# ballanced_detector.net
KiCad netlist of a schematic drawn in EAGLE
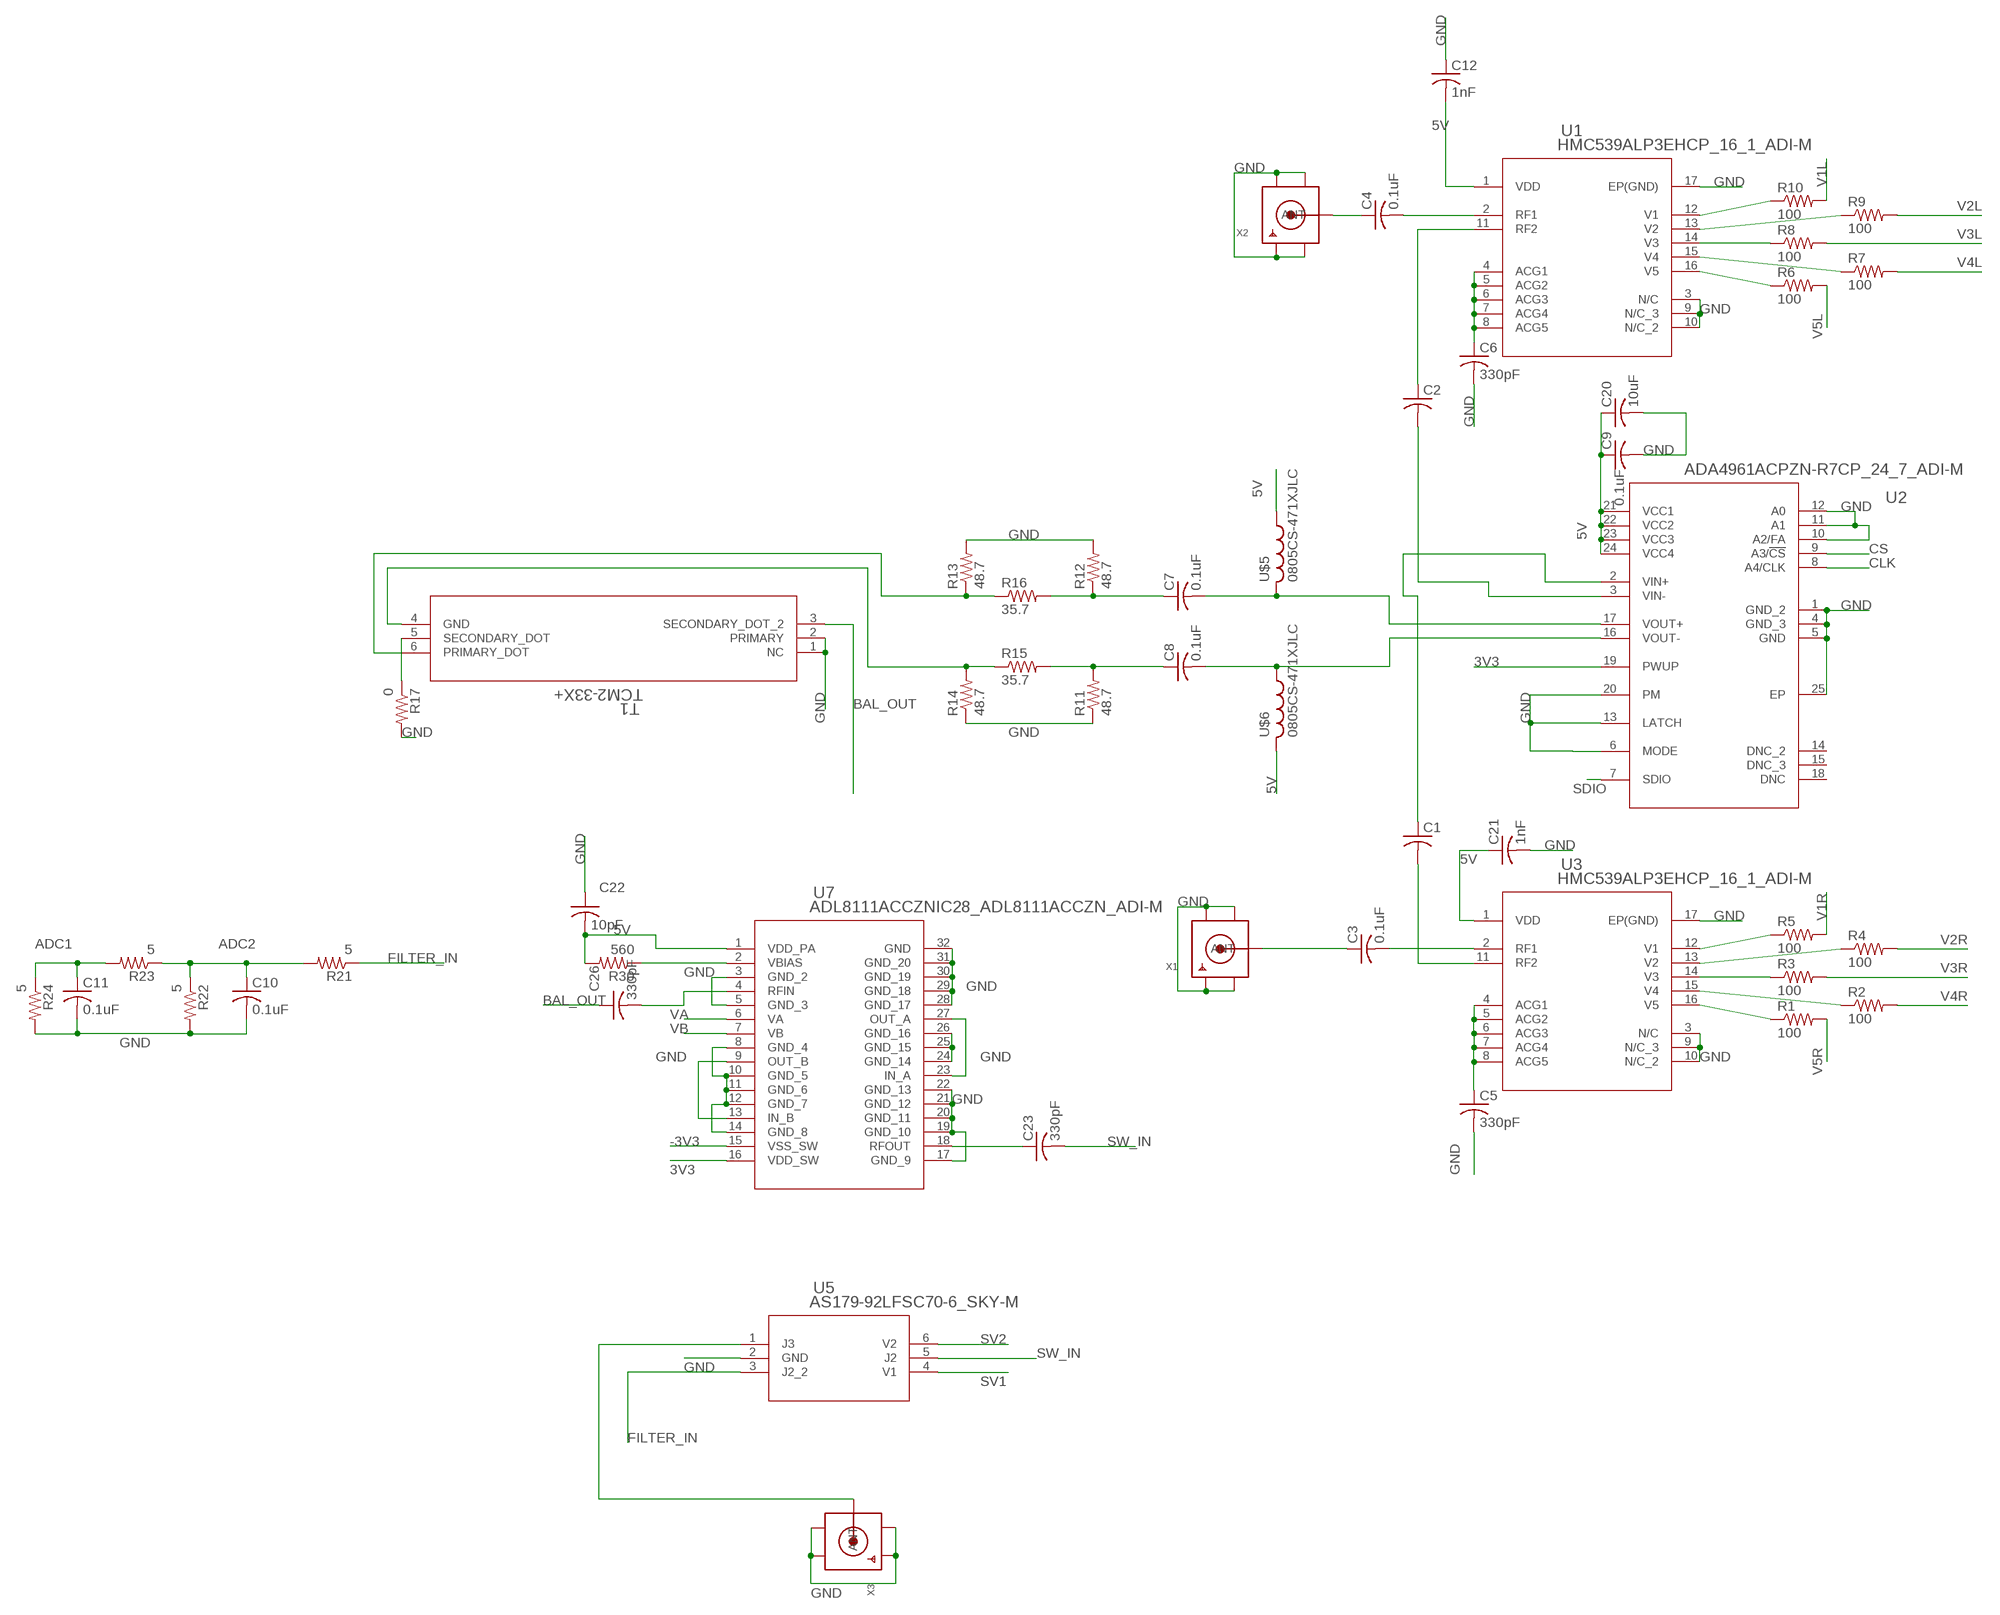
[diagram p0: schematic, sheet 1, part 1 of 2]
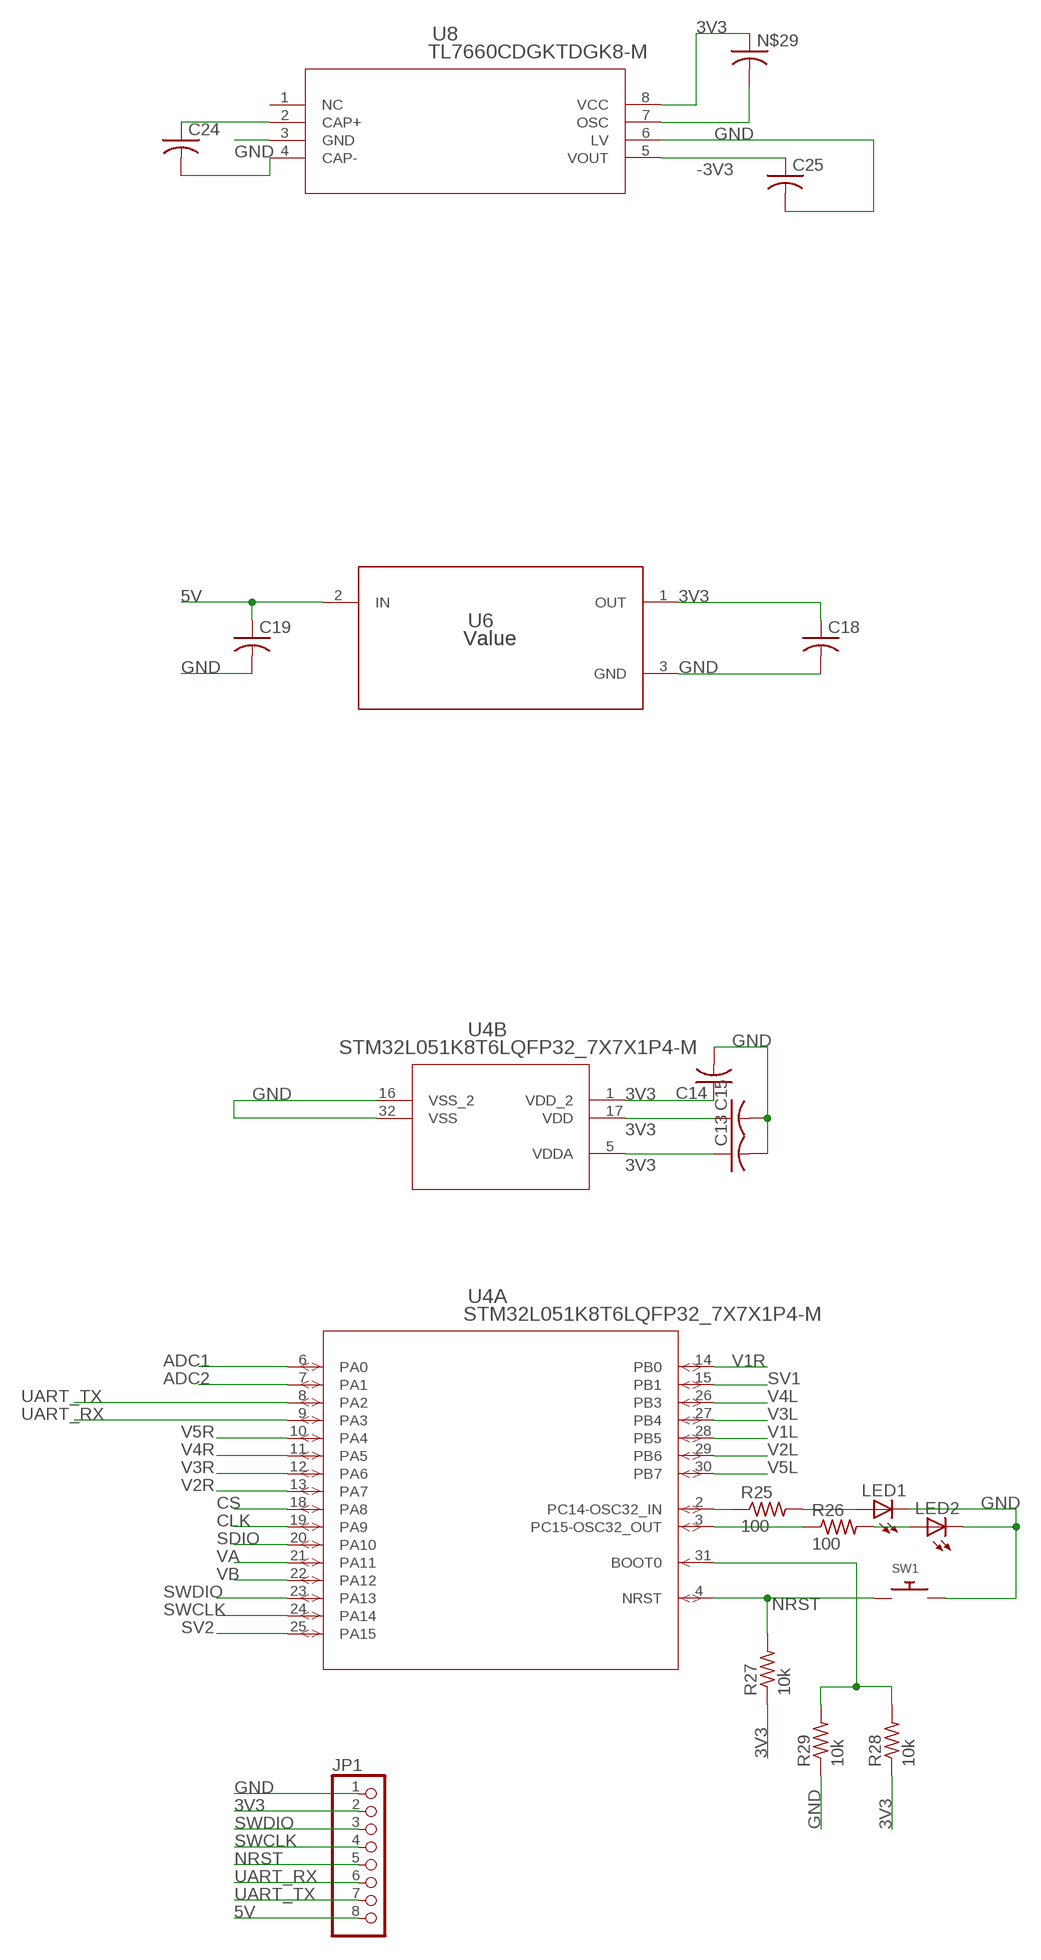
[diagram p1: schematic, sheet 1, part 2 of 2]

(export (version "E")
  (design (tool "Eeschema 10.0.6"))
  (components
    (comp (ref "C1")
      (value "C-USC0402")
      (footprint "eagle-import:C0402")
      (libsource (lib "eagle-import") (part "C-USC0402"))
    )
    (comp (ref "C2")
      (value "C-USC0402")
      (footprint "eagle-import:C0402")
      (libsource (lib "eagle-import") (part "C-USC0402"))
    )
    (comp (ref "C3")
      (value "0.1uF")
      (footprint "eagle-import:C0402")
      (libsource (lib "eagle-import") (part "C-USC0402"))
    )
    (comp (ref "C4")
      (value "0.1uF")
      (footprint "eagle-import:C0402")
      (libsource (lib "eagle-import") (part "C-USC0402"))
    )
    (comp (ref "C5")
      (value "330pF")
      (footprint "eagle-import:C0402")
      (libsource (lib "eagle-import") (part "C-USC0402"))
    )
    (comp (ref "C6")
      (value "330pF")
      (footprint "eagle-import:C0402")
      (libsource (lib "eagle-import") (part "C-USC0402"))
    )
    (comp (ref "C7")
      (value "0.1uF")
      (footprint "eagle-import:C0402")
      (libsource (lib "eagle-import") (part "C-USC0402"))
    )
    (comp (ref "C8")
      (value "0.1uF")
      (footprint "eagle-import:C0402")
      (libsource (lib "eagle-import") (part "C-USC0402"))
    )
    (comp (ref "C9")
      (value "0.1uF")
      (footprint "eagle-import:C0402")
      (libsource (lib "eagle-import") (part "C-USC0402"))
    )
    (comp (ref "C10")
      (value "0.1uF")
      (footprint "eagle-import:C0402")
      (libsource (lib "eagle-import") (part "C-USC0402"))
    )
    (comp (ref "C11")
      (value "0.1uF")
      (footprint "eagle-import:C0402")
      (libsource (lib "eagle-import") (part "C-USC0402"))
    )
    (comp (ref "C12")
      (value "1nF")
      (footprint "eagle-import:C0402")
      (libsource (lib "eagle-import") (part "C-USC0402"))
    )
    (comp (ref "C13")
      (value "C-USC0402")
      (footprint "eagle-import:C0402")
      (libsource (lib "eagle-import") (part "C-USC0402"))
    )
    (comp (ref "C14")
      (value "C-USC0402")
      (footprint "eagle-import:C0402")
      (libsource (lib "eagle-import") (part "C-USC0402"))
    )
    (comp (ref "C15")
      (value "C-USC0402")
      (footprint "eagle-import:C0402")
      (libsource (lib "eagle-import") (part "C-USC0402"))
    )
    (comp (ref "C18")
      (value "C-USC0402")
      (footprint "eagle-import:C0402")
      (libsource (lib "eagle-import") (part "C-USC0402"))
    )
    (comp (ref "C19")
      (value "C-USC0402")
      (footprint "eagle-import:C0402")
      (libsource (lib "eagle-import") (part "C-USC0402"))
    )
    (comp (ref "C20")
      (value "10uF")
      (footprint "eagle-import:C0402")
      (libsource (lib "eagle-import") (part "C-USC0402"))
    )
    (comp (ref "C21")
      (value "1nF")
      (footprint "eagle-import:C0402")
      (libsource (lib "eagle-import") (part "C-USC0402"))
    )
    (comp (ref "C22")
      (value "10pF")
      (footprint "eagle-import:C0402")
      (libsource (lib "eagle-import") (part "C-USC0402"))
    )
    (comp (ref "C23")
      (value "330pF")
      (footprint "eagle-import:C0402")
      (libsource (lib "eagle-import") (part "C-USC0402"))
    )
    (comp (ref "C24")
      (value "C-USC1210")
      (footprint "eagle-import:C1210")
      (libsource (lib "eagle-import") (part "C-USC1210"))
    )
    (comp (ref "C25")
      (value "C-USC1210")
      (footprint "eagle-import:C1210")
      (libsource (lib "eagle-import") (part "C-USC1210"))
    )
    (comp (ref "C26")
      (value "330pF")
      (footprint "eagle-import:C0402")
      (libsource (lib "eagle-import") (part "C-USC0402"))
    )
    (comp (ref "JP1")
      (value "PINHD-1X8CLEANBIG")
      (footprint "eagle-import:1X08-CLEANBIG")
      (libsource (lib "eagle-import") (part "PINHD-1X8CLEANBIG"))
    )
    (comp (ref "LED1")
      (value "LEDCHIP-LED0805")
      (footprint "eagle-import:CHIP-LED0805")
      (libsource (lib "eagle-import") (part "LEDCHIP-LED0805"))
    )
    (comp (ref "LED2")
      (value "LEDCHIP-LED0805")
      (footprint "eagle-import:CHIP-LED0805")
      (libsource (lib "eagle-import") (part "LEDCHIP-LED0805"))
    )
    (comp (ref "N$29")
      (value "C-USC1210")
      (footprint "eagle-import:C1210")
      (libsource (lib "eagle-import") (part "C-USC1210"))
    )
    (comp (ref "R1")
      (value "100")
      (footprint "eagle-import:R0402")
      (libsource (lib "eagle-import") (part "R-US_R0402"))
    )
    (comp (ref "R2")
      (value "100")
      (footprint "eagle-import:R0402")
      (libsource (lib "eagle-import") (part "R-US_R0402"))
    )
    (comp (ref "R3")
      (value "100")
      (footprint "eagle-import:R0402")
      (libsource (lib "eagle-import") (part "R-US_R0402"))
    )
    (comp (ref "R4")
      (value "100")
      (footprint "eagle-import:R0402")
      (libsource (lib "eagle-import") (part "R-US_R0402"))
    )
    (comp (ref "R5")
      (value "100")
      (footprint "eagle-import:R0402")
      (libsource (lib "eagle-import") (part "R-US_R0402"))
    )
    (comp (ref "R6")
      (value "100")
      (footprint "eagle-import:R0402")
      (libsource (lib "eagle-import") (part "R-US_R0402"))
    )
    (comp (ref "R7")
      (value "100")
      (footprint "eagle-import:R0402")
      (libsource (lib "eagle-import") (part "R-US_R0402"))
    )
    (comp (ref "R8")
      (value "100")
      (footprint "eagle-import:R0402")
      (libsource (lib "eagle-import") (part "R-US_R0402"))
    )
    (comp (ref "R9")
      (value "100")
      (footprint "eagle-import:R0402")
      (libsource (lib "eagle-import") (part "R-US_R0402"))
    )
    (comp (ref "R10")
      (value "100")
      (footprint "eagle-import:R0402")
      (libsource (lib "eagle-import") (part "R-US_R0402"))
    )
    (comp (ref "R11")
      (value "48.7")
      (footprint "eagle-import:R0402")
      (libsource (lib "eagle-import") (part "R-US_R0402"))
    )
    (comp (ref "R12")
      (value "48.7")
      (footprint "eagle-import:R0402")
      (libsource (lib "eagle-import") (part "R-US_R0402"))
    )
    (comp (ref "R13")
      (value "48.7")
      (footprint "eagle-import:R0402")
      (libsource (lib "eagle-import") (part "R-US_R0402"))
    )
    (comp (ref "R14")
      (value "48.7")
      (footprint "eagle-import:R0402")
      (libsource (lib "eagle-import") (part "R-US_R0402"))
    )
    (comp (ref "R15")
      (value "35.7")
      (footprint "eagle-import:R0402")
      (libsource (lib "eagle-import") (part "R-US_R0402"))
    )
    (comp (ref "R16")
      (value "35.7")
      (footprint "eagle-import:R0402")
      (libsource (lib "eagle-import") (part "R-US_R0402"))
    )
    (comp (ref "R17")
      (value "0")
      (footprint "eagle-import:R0402")
      (libsource (lib "eagle-import") (part "R-US_R0402"))
    )
    (comp (ref "R21")
      (value "5")
      (footprint "eagle-import:R0402")
      (libsource (lib "eagle-import") (part "R-US_R0402"))
    )
    (comp (ref "R22")
      (value "5")
      (footprint "eagle-import:R0402")
      (libsource (lib "eagle-import") (part "R-US_R0402"))
    )
    (comp (ref "R23")
      (value "5")
      (footprint "eagle-import:R0402")
      (libsource (lib "eagle-import") (part "R-US_R0402"))
    )
    (comp (ref "R24")
      (value "5")
      (footprint "eagle-import:R0402")
      (libsource (lib "eagle-import") (part "R-US_R0402"))
    )
    (comp (ref "R25")
      (value "100")
      (footprint "eagle-import:R0402")
      (libsource (lib "eagle-import") (part "R-US_R0402"))
    )
    (comp (ref "R26")
      (value "100")
      (footprint "eagle-import:R0402")
      (libsource (lib "eagle-import") (part "R-US_R0402"))
    )
    (comp (ref "R27")
      (value "10k")
      (footprint "eagle-import:R0402")
      (libsource (lib "eagle-import") (part "R-US_R0402"))
    )
    (comp (ref "R28")
      (value "10k")
      (footprint "eagle-import:R0402")
      (libsource (lib "eagle-import") (part "R-US_R0402"))
    )
    (comp (ref "R29")
      (value "10k")
      (footprint "eagle-import:R0402")
      (libsource (lib "eagle-import") (part "R-US_R0402"))
    )
    (comp (ref "R30")
      (value "560")
      (footprint "eagle-import:R0402")
      (libsource (lib "eagle-import") (part "R-US_R0402"))
    )
    (comp (ref "SW1")
      (value "SWITCH_PUSHBUTTONC&K_KSS")
      (footprint "eagle-import:BTN_CK_KSS")
      (libsource (lib "eagle-import") (part "SWITCH_PUSHBUTTONC&K_KSS"))
    )
    (comp (ref "T1")
      (value "TCM2-33X+")
      (footprint "eagle-import:DB1627_MNC")
      (fields (field (name "COPYRIGHT") "Copyright (C) 2018 Accelerated Designs. All rights reserved"))
      (libsource (lib "eagle-import") (part "TCM2-33X+"))
    )
    (comp (ref "U$5")
      (value "0805CS-471XJLC")
      (footprint "eagle-import:R0805")
      (libsource (lib "eagle-import") (part "0805CS-471XJLC"))
    )
    (comp (ref "U$6")
      (value "0805CS-471XJLC")
      (footprint "eagle-import:R0805")
      (libsource (lib "eagle-import") (part "0805CS-471XJLC"))
    )
    (comp (ref "U1")
      (value "HMC539ALP3EHCP_16_1_ADI-M")
      (footprint "eagle-import:HCP_16_1_ADI-M")
      (fields (field (name "MANUFACTURER_PART_NUMBER") "HMC539ALP3E"))
      (libsource (lib "eagle-import") (part "HMC539ALP3EHCP_16_1_ADI-M"))
    )
    (comp (ref "U2")
      (value "ADA4961ACPZN-R7CP_24_7_ADI-M")
      (footprint "eagle-import:CP_24_7_ADI-M")
      (fields (field (name "MANUFACTURER_PART_NUMBER") "ADA4961ACPZN-R7"))
      (libsource (lib "eagle-import") (part "ADA4961ACPZN-R7CP_24_7_ADI-M"))
    )
    (comp (ref "U3")
      (value "HMC539ALP3EHCP_16_1_ADI-M")
      (footprint "eagle-import:HCP_16_1_ADI-M")
      (fields (field (name "MANUFACTURER_PART_NUMBER") "HMC539ALP3E"))
      (libsource (lib "eagle-import") (part "HMC539ALP3EHCP_16_1_ADI-M"))
    )
    (comp (ref "U4")
      (value "STM32L051K8T6LQFP32_7X7X1P4-M")
      (footprint "eagle-import:LQFP32_7X7X1P4-M")
      (fields
        (field (name "MANUFACTURER_PART_NUMBER") "STM32L051K8T6")
        (field (name "COPYRIGHT") "Copyright (C) 2018 Accelerated Designs. All rights reserved")
      )
      (libsource (lib "eagle-import") (part "STM32L051K8T6LQFP32_7X7X1P4-M"))
    )
    (comp (ref "U5")
      (value "AS179-92LFSC70-6_SKY-M")
      (footprint "eagle-import:SC70-6_SKY-M")
      (fields
        (field (name "MANUFACTURER_PART_NUMBER") "AS179-92LF")
        (field (name "COPYRIGHT") "Copyright (C) 2016 Accelerated Designs. All rights reserved")
      )
      (libsource (lib "eagle-import") (part "AS179-92LFSC70-6_SKY-M"))
    )
    (comp (ref "U6")
      (value "Value")
      (footprint "eagle-import:DBZ0003A_N")
      (fields
        (field (name "MANUFACTURER") "Texas Instruments")
        (field (name "PARTNUMBER") "LM3480IM3X-3.3/NOPB")
      )
      (libsource (lib "eagle-import") (part "LM3480IM3-3.3"))
    )
    (comp (ref "U7")
      (value "ADL8111ACCZNIC28_ADL8111ACCZN_ADI-M")
      (footprint "eagle-import:IC28_ADL8111ACCZN_ADI-M")
      (fields
        (field (name "MANUFACTURER_PART_NUMBER") "ADL8111ACCZN")
        (field (name "COPYRIGHT") "Copyright (C) 2018 Accelerated Designs. All rights reserved")
      )
      (libsource (lib "eagle-import") (part "ADL8111ACCZNIC28_ADL8111ACCZN_ADI-M"))
    )
    (comp (ref "U8")
      (value "TL7660CDGKTDGK8-M")
      (footprint "eagle-import:DGK8-M")
      (fields
        (field (name "GENERIC_PART_NUMBER") "TL7660")
        (field (name "MANUFACTURER") "Texas Instruments")
        (field (name "MANUFACTURER_PART_NUMBER") "TL7660CDGKT")
      )
      (libsource (lib "eagle-import") (part "TL7660CDGKTDGK8-M"))
    )
    (comp (ref "X1")
      (value "SMACONNECTOR_EDGE")
      (footprint "eagle-import:SMA_EDGELAUNCH")
      (libsource (lib "eagle-import") (part "SMACONNECTOR_EDGE"))
    )
    (comp (ref "X2")
      (value "SMACONNECTOR_EDGE")
      (footprint "eagle-import:SMA_EDGELAUNCH")
      (libsource (lib "eagle-import") (part "SMACONNECTOR_EDGE"))
    )
    (comp (ref "X3")
      (value "SMACONNECTOR_EDGE")
      (footprint "eagle-import:SMA_EDGELAUNCH")
      (libsource (lib "eagle-import") (part "SMACONNECTOR_EDGE"))
    )
  )
  (nets
    (net (code "1") (name "/-3V3") (class "Default")
      (node (ref "C25") (pin "1") (pinfunction "1_1") (pintype "passive"))
      (node (ref "U7") (pin "15") (pinfunction "VSS_SW_15") (pintype "passive"))
      (node (ref "U8") (pin "5") (pinfunction "VOUT_5") (pintype "output"))
    )
    (net (code "2") (name "/3V3") (class "Default")
      (node (ref "C13") (pin "1") (pinfunction "1_1") (pintype "passive"))
      (node (ref "C14") (pin "1") (pinfunction "1_1") (pintype "passive"))
      (node (ref "C15") (pin "1") (pinfunction "1_1") (pintype "passive"))
      (node (ref "C18") (pin "1") (pinfunction "1_1") (pintype "passive"))
      (node (ref "JP1") (pin "2") (pinfunction "2_2") (pintype "passive"))
      (node (ref "N$29") (pin "1") (pinfunction "1_1") (pintype "passive"))
      (node (ref "R27") (pin "1") (pinfunction "1_1") (pintype "passive"))
      (node (ref "R28") (pin "1") (pinfunction "1_1") (pintype "passive"))
      (node (ref "U2") (pin "19") (pinfunction "PWUP_19") (pintype "passive"))
      (node (ref "U4") (pin "1") (pinfunction "VDD_2_1") (pintype "power_in"))
      (node (ref "U4") (pin "17") (pinfunction "VDD_17") (pintype "power_in"))
      (node (ref "U4") (pin "5") (pinfunction "VDDA_5") (pintype "power_in"))
      (node (ref "U6") (pin "1") (pinfunction "OUT_1") (pintype "power_in"))
      (node (ref "U7") (pin "16") (pinfunction "VDD_SW_16") (pintype "power_in"))
      (node (ref "U8") (pin "8") (pinfunction "VCC_8") (pintype "power_in"))
    )
    (net (code "3") (name "/5V") (class "Default")
      (node (ref "C12") (pin "2") (pinfunction "2_2") (pintype "passive"))
      (node (ref "C19") (pin "1") (pinfunction "1_1") (pintype "passive"))
      (node (ref "C20") (pin "1") (pinfunction "1_1") (pintype "passive"))
      (node (ref "C21") (pin "1") (pinfunction "1_1") (pintype "passive"))
      (node (ref "C22") (pin "2") (pinfunction "2_2") (pintype "passive"))
      (node (ref "C9") (pin "1") (pinfunction "1_1") (pintype "passive"))
      (node (ref "JP1") (pin "8") (pinfunction "8_8") (pintype "passive"))
      (node (ref "R30") (pin "2") (pinfunction "2_2") (pintype "passive"))
      (node (ref "U$5") (pin "1") (pinfunction "1_1") (pintype "passive"))
      (node (ref "U$6") (pin "2") (pinfunction "2_2") (pintype "passive"))
      (node (ref "U1") (pin "1") (pinfunction "VDD_1") (pintype "passive"))
      (node (ref "U2") (pin "21") (pinfunction "VCC1_21") (pintype "passive"))
      (node (ref "U2") (pin "22") (pinfunction "VCC2_22") (pintype "passive"))
      (node (ref "U2") (pin "23") (pinfunction "VCC3_23") (pintype "passive"))
      (node (ref "U2") (pin "24") (pinfunction "VCC4_24") (pintype "passive"))
      (node (ref "U3") (pin "1") (pinfunction "VDD_1") (pintype "passive"))
      (node (ref "U6") (pin "2") (pinfunction "IN_2") (pintype "power_in"))
      (node (ref "U7") (pin "1") (pinfunction "VDD_PA_1") (pintype "power_in"))
    )
    (net (code "4") (name "/ADC1") (class "Default")
      (node (ref "C11") (pin "1") (pinfunction "1_1") (pintype "passive"))
      (node (ref "R23") (pin "2") (pinfunction "2_2") (pintype "passive"))
      (node (ref "R24") (pin "1") (pinfunction "1_1") (pintype "passive"))
      (node (ref "U4") (pin "6") (pinfunction "PA0_6") (pintype "bidirectional"))
    )
    (net (code "5") (name "/ADC2") (class "Default")
      (node (ref "C10") (pin "1") (pinfunction "1_1") (pintype "passive"))
      (node (ref "R21") (pin "2") (pinfunction "2_2") (pintype "passive"))
      (node (ref "R22") (pin "1") (pinfunction "1_1") (pintype "passive"))
      (node (ref "R23") (pin "1") (pinfunction "1_1") (pintype "passive"))
      (node (ref "U4") (pin "7") (pinfunction "PA1_7") (pintype "bidirectional"))
    )
    (net (code "6") (name "/BAL_OUT") (class "Default")
      (node (ref "C26") (pin "1") (pinfunction "1_1") (pintype "passive"))
      (node (ref "T1") (pin "3") (pinfunction "SECONDARY_DOT_2_3") (pintype "passive"))
    )
    (net (code "7") (name "/CLK") (class "Default")
      (node (ref "U2") (pin "8") (pinfunction "A4/CLK_8") (pintype "passive"))
      (node (ref "U4") (pin "19") (pinfunction "PA9_19") (pintype "bidirectional"))
    )
    (net (code "8") (name "/CS") (class "Default")
      (node (ref "U2") (pin "9") (pinfunction "A3/~{CS}_9") (pintype "passive"))
      (node (ref "U4") (pin "18") (pinfunction "PA8_18") (pintype "bidirectional"))
    )
    (net (code "9") (name "/FILTER_IN") (class "Default")
      (node (ref "R21") (pin "1") (pinfunction "1_1") (pintype "passive"))
      (node (ref "U5") (pin "3") (pinfunction "J2_2_3") (pintype "passive"))
    )
    (net (code "10") (name "/GND") (class "Default")
      (node (ref "C10") (pin "2") (pinfunction "2_2") (pintype "passive"))
      (node (ref "C11") (pin "2") (pinfunction "2_2") (pintype "passive"))
      (node (ref "C12") (pin "1") (pinfunction "1_1") (pintype "passive"))
      (node (ref "C13") (pin "2") (pinfunction "2_2") (pintype "passive"))
      (node (ref "C14") (pin "2") (pinfunction "2_2") (pintype "passive"))
      (node (ref "C15") (pin "2") (pinfunction "2_2") (pintype "passive"))
      (node (ref "C18") (pin "2") (pinfunction "2_2") (pintype "passive"))
      (node (ref "C19") (pin "2") (pinfunction "2_2") (pintype "passive"))
      (node (ref "C20") (pin "2") (pinfunction "2_2") (pintype "passive"))
      (node (ref "C21") (pin "2") (pinfunction "2_2") (pintype "passive"))
      (node (ref "C22") (pin "1") (pinfunction "1_1") (pintype "passive"))
      (node (ref "C25") (pin "2") (pinfunction "2_2") (pintype "passive"))
      (node (ref "C5") (pin "2") (pinfunction "2_2") (pintype "passive"))
      (node (ref "C6") (pin "2") (pinfunction "2_2") (pintype "passive"))
      (node (ref "C9") (pin "2") (pinfunction "2_2") (pintype "passive"))
      (node (ref "JP1") (pin "1") (pinfunction "1_1") (pintype "passive"))
      (node (ref "LED1") (pin "C") (pinfunction "C_C") (pintype "passive"))
      (node (ref "LED2") (pin "C") (pinfunction "C_C") (pintype "passive"))
      (node (ref "R11") (pin "1") (pinfunction "1_1") (pintype "passive"))
      (node (ref "R12") (pin "2") (pinfunction "2_2") (pintype "passive"))
      (node (ref "R13") (pin "2") (pinfunction "2_2") (pintype "passive"))
      (node (ref "R14") (pin "1") (pinfunction "1_1") (pintype "passive"))
      (node (ref "R17") (pin "2") (pinfunction "2_2") (pintype "passive"))
      (node (ref "R22") (pin "2") (pinfunction "2_2") (pintype "passive"))
      (node (ref "R24") (pin "2") (pinfunction "2_2") (pintype "passive"))
      (node (ref "R29") (pin "1") (pinfunction "1_1") (pintype "passive"))
      (node (ref "SW1") (pin "P$2") (pinfunction "P$2_P$2") (pintype "passive"))
      (node (ref "T1") (pin "1") (pinfunction "NC_1") (pintype "passive"))
      (node (ref "T1") (pin "2") (pinfunction "PRIMARY_2") (pintype "passive"))
      (node (ref "U1") (pin "10") (pinfunction "N/C_2_10") (pintype "passive"))
      (node (ref "U1") (pin "17") (pinfunction "EP(GND)_17") (pintype "passive"))
      (node (ref "U1") (pin "3") (pinfunction "N/C_3") (pintype "passive"))
      (node (ref "U1") (pin "9") (pinfunction "N/C_3_9") (pintype "passive"))
      (node (ref "U2") (pin "1") (pinfunction "GND_2_1") (pintype "passive"))
      (node (ref "U2") (pin "10") (pinfunction "A2/FA_10") (pintype "passive"))
      (node (ref "U2") (pin "11") (pinfunction "A1_11") (pintype "passive"))
      (node (ref "U2") (pin "12") (pinfunction "A0_12") (pintype "passive"))
      (node (ref "U2") (pin "13") (pinfunction "LATCH_13") (pintype "passive"))
      (node (ref "U2") (pin "20") (pinfunction "PM_20") (pintype "passive"))
      (node (ref "U2") (pin "25") (pinfunction "EP_25") (pintype "passive"))
      (node (ref "U2") (pin "4") (pinfunction "GND_3_4") (pintype "passive"))
      (node (ref "U2") (pin "5") (pinfunction "GND_5") (pintype "passive"))
      (node (ref "U2") (pin "6") (pinfunction "MODE_6") (pintype "passive"))
      (node (ref "U3") (pin "10") (pinfunction "N/C_2_10") (pintype "passive"))
      (node (ref "U3") (pin "17") (pinfunction "EP(GND)_17") (pintype "passive"))
      (node (ref "U3") (pin "3") (pinfunction "N/C_3") (pintype "passive"))
      (node (ref "U3") (pin "9") (pinfunction "N/C_3_9") (pintype "passive"))
      (node (ref "U4") (pin "16") (pinfunction "VSS_2_16") (pintype "power_in"))
      (node (ref "U4") (pin "32") (pinfunction "VSS_32") (pintype "power_in"))
      (node (ref "U5") (pin "2") (pinfunction "GND_2") (pintype "power_in"))
      (node (ref "U6") (pin "3") (pinfunction "GND_3") (pintype "power_in"))
      (node (ref "U7") (pin "10") (pinfunction "GND_5_10") (pintype "passive"))
      (node (ref "U7") (pin "11") (pinfunction "GND_6_11") (pintype "passive"))
      (node (ref "U7") (pin "12") (pinfunction "GND_7_12") (pintype "passive"))
      (node (ref "U7") (pin "14") (pinfunction "GND_8_14") (pintype "passive"))
      (node (ref "U7") (pin "17") (pinfunction "GND_9_17") (pintype "passive"))
      (node (ref "U7") (pin "19") (pinfunction "GND_10_19") (pintype "passive"))
      (node (ref "U7") (pin "20") (pinfunction "GND_11_20") (pintype "passive"))
      (node (ref "U7") (pin "21") (pinfunction "GND_12_21") (pintype "passive"))
      (node (ref "U7") (pin "22") (pinfunction "GND_13_22") (pintype "passive"))
      (node (ref "U7") (pin "24") (pinfunction "GND_14_24") (pintype "passive"))
      (node (ref "U7") (pin "25") (pinfunction "GND_15_25") (pintype "passive"))
      (node (ref "U7") (pin "26") (pinfunction "GND_16_26") (pintype "passive"))
      (node (ref "U7") (pin "28") (pinfunction "GND_17_28") (pintype "passive"))
      (node (ref "U7") (pin "29") (pinfunction "GND_18_29") (pintype "passive"))
      (node (ref "U7") (pin "3") (pinfunction "GND_2_3") (pintype "passive"))
      (node (ref "U7") (pin "30") (pinfunction "GND_19_30") (pintype "passive"))
      (node (ref "U7") (pin "31") (pinfunction "GND_20_31") (pintype "passive"))
      (node (ref "U7") (pin "32") (pinfunction "GND_32") (pintype "passive"))
      (node (ref "U7") (pin "5") (pinfunction "GND_3_5") (pintype "passive"))
      (node (ref "U7") (pin "8") (pinfunction "GND_4_8") (pintype "passive"))
      (node (ref "U8") (pin "3") (pinfunction "GND_3") (pintype "power_in"))
      (node (ref "U8") (pin "6") (pinfunction "LV_6") (pintype "passive"))
      (node (ref "X1") (pin "GND@1") (pinfunction "GND4_GND@1") (pintype "power_in"))
      (node (ref "X1") (pin "GND@2") (pinfunction "GND3_GND@2") (pintype "power_in"))
      (node (ref "X1") (pin "GND@3") (pinfunction "GND2_GND@3") (pintype "power_in"))
      (node (ref "X1") (pin "GND@4") (pinfunction "GND1_GND@4") (pintype "power_in"))
      (node (ref "X2") (pin "GND@1") (pinfunction "GND4_GND@1") (pintype "power_in"))
      (node (ref "X2") (pin "GND@2") (pinfunction "GND3_GND@2") (pintype "power_in"))
      (node (ref "X2") (pin "GND@3") (pinfunction "GND2_GND@3") (pintype "power_in"))
      (node (ref "X2") (pin "GND@4") (pinfunction "GND1_GND@4") (pintype "power_in"))
      (node (ref "X3") (pin "GND@1") (pinfunction "GND4_GND@1") (pintype "power_in"))
      (node (ref "X3") (pin "GND@2") (pinfunction "GND3_GND@2") (pintype "power_in"))
      (node (ref "X3") (pin "GND@3") (pinfunction "GND2_GND@3") (pintype "power_in"))
      (node (ref "X3") (pin "GND@4") (pinfunction "GND1_GND@4") (pintype "power_in"))
    )
    (net (code "11") (name "/NRST") (class "Default")
      (node (ref "JP1") (pin "5") (pinfunction "5_5") (pintype "passive"))
      (node (ref "R27") (pin "2") (pinfunction "2_2") (pintype "passive"))
      (node (ref "SW1") (pin "P$1") (pinfunction "P$1_P$1") (pintype "passive"))
      (node (ref "U4") (pin "4") (pinfunction "NRST_4") (pintype "bidirectional"))
    )
    (net (code "12") (name "/SDIO") (class "Default")
      (node (ref "U2") (pin "7") (pinfunction "SDIO_7") (pintype "passive"))
      (node (ref "U4") (pin "20") (pinfunction "PA10_20") (pintype "bidirectional"))
    )
    (net (code "13") (name "/SV1") (class "Default")
      (node (ref "U4") (pin "15") (pinfunction "PB1_15") (pintype "bidirectional"))
      (node (ref "U5") (pin "4") (pinfunction "V1_4") (pintype "passive"))
    )
    (net (code "14") (name "/SV2") (class "Default")
      (node (ref "U4") (pin "25") (pinfunction "PA15_25") (pintype "bidirectional"))
      (node (ref "U5") (pin "6") (pinfunction "V2_6") (pintype "passive"))
    )
    (net (code "15") (name "/SWCLK") (class "Default")
      (node (ref "JP1") (pin "4") (pinfunction "4_4") (pintype "passive"))
      (node (ref "U4") (pin "24") (pinfunction "PA14_24") (pintype "bidirectional"))
    )
    (net (code "16") (name "/SWDIO") (class "Default")
      (node (ref "JP1") (pin "3") (pinfunction "3_3") (pintype "passive"))
      (node (ref "U4") (pin "23") (pinfunction "PA13_23") (pintype "bidirectional"))
    )
    (net (code "17") (name "/SW_IN") (class "Default")
      (node (ref "C23") (pin "2") (pinfunction "2_2") (pintype "passive"))
      (node (ref "U5") (pin "5") (pinfunction "J2_5") (pintype "passive"))
    )
    (net (code "18") (name "/UART_RX") (class "Default")
      (node (ref "JP1") (pin "6") (pinfunction "6_6") (pintype "passive"))
      (node (ref "U4") (pin "9") (pinfunction "PA3_9") (pintype "bidirectional"))
    )
    (net (code "19") (name "/UART_TX") (class "Default")
      (node (ref "JP1") (pin "7") (pinfunction "7_7") (pintype "passive"))
      (node (ref "U4") (pin "8") (pinfunction "PA2_8") (pintype "bidirectional"))
    )
    (net (code "20") (name "/V1L") (class "Default")
      (node (ref "R10") (pin "2") (pinfunction "2_2") (pintype "passive"))
      (node (ref "U4") (pin "28") (pinfunction "PB5_28") (pintype "bidirectional"))
    )
    (net (code "21") (name "/V1R") (class "Default")
      (node (ref "R5") (pin "2") (pinfunction "2_2") (pintype "passive"))
      (node (ref "U4") (pin "14") (pinfunction "PB0_14") (pintype "bidirectional"))
    )
    (net (code "22") (name "/V2L") (class "Default")
      (node (ref "R9") (pin "2") (pinfunction "2_2") (pintype "passive"))
      (node (ref "U4") (pin "29") (pinfunction "PB6_29") (pintype "bidirectional"))
    )
    (net (code "23") (name "/V2R") (class "Default")
      (node (ref "R4") (pin "2") (pinfunction "2_2") (pintype "passive"))
      (node (ref "U4") (pin "13") (pinfunction "PA7_13") (pintype "bidirectional"))
    )
    (net (code "24") (name "/V3L") (class "Default")
      (node (ref "R8") (pin "2") (pinfunction "2_2") (pintype "passive"))
      (node (ref "U4") (pin "27") (pinfunction "PB4_27") (pintype "bidirectional"))
    )
    (net (code "25") (name "/V3R") (class "Default")
      (node (ref "R3") (pin "2") (pinfunction "2_2") (pintype "passive"))
      (node (ref "U4") (pin "12") (pinfunction "PA6_12") (pintype "bidirectional"))
    )
    (net (code "26") (name "/V4L") (class "Default")
      (node (ref "R7") (pin "2") (pinfunction "2_2") (pintype "passive"))
      (node (ref "U4") (pin "26") (pinfunction "PB3_26") (pintype "bidirectional"))
    )
    (net (code "27") (name "/V4R") (class "Default")
      (node (ref "R2") (pin "2") (pinfunction "2_2") (pintype "passive"))
      (node (ref "U4") (pin "11") (pinfunction "PA5_11") (pintype "bidirectional"))
    )
    (net (code "28") (name "/V5L") (class "Default")
      (node (ref "R6") (pin "2") (pinfunction "2_2") (pintype "passive"))
      (node (ref "U4") (pin "30") (pinfunction "PB7_30") (pintype "bidirectional"))
    )
    (net (code "29") (name "/V5R") (class "Default")
      (node (ref "R1") (pin "2") (pinfunction "2_2") (pintype "passive"))
      (node (ref "U4") (pin "10") (pinfunction "PA4_10") (pintype "bidirectional"))
    )
    (net (code "30") (name "/VA") (class "Default")
      (node (ref "U4") (pin "21") (pinfunction "PA11_21") (pintype "bidirectional"))
      (node (ref "U7") (pin "6") (pinfunction "VA_6") (pintype "passive"))
    )
    (net (code "31") (name "/VB") (class "Default")
      (node (ref "U4") (pin "22") (pinfunction "PA12_22") (pintype "bidirectional"))
      (node (ref "U7") (pin "7") (pinfunction "VB_7") (pintype "passive"))
    )
    (net (code "32") (name "Net-(C7-Pad1)") (class "Default")
      (node (ref "C7") (pin "1") (pinfunction "1_1") (pintype "passive"))
      (node (ref "R12") (pin "1") (pinfunction "1_1") (pintype "passive"))
      (node (ref "R16") (pin "2") (pinfunction "2_2") (pintype "passive"))
    )
    (net (code "33") (name "Net-(C8-Pad1)") (class "Default")
      (node (ref "C8") (pin "1") (pinfunction "1_1") (pintype "passive"))
      (node (ref "R11") (pin "2") (pinfunction "2_2") (pintype "passive"))
      (node (ref "R15") (pin "2") (pinfunction "2_2") (pintype "passive"))
    )
    (net (code "34") (name "Net-(LED1-PadA)") (class "Default")
      (node (ref "LED1") (pin "A") (pinfunction "A_A") (pintype "passive"))
      (node (ref "R25") (pin "2") (pinfunction "2_2") (pintype "passive"))
    )
    (net (code "35") (name "Net-(LED2-PadA)") (class "Default")
      (node (ref "LED2") (pin "A") (pinfunction "A_A") (pintype "passive"))
      (node (ref "R26") (pin "2") (pinfunction "2_2") (pintype "passive"))
    )
    (net (code "36") (name "Net-(T1-GND)") (class "Default")
      (node (ref "R14") (pin "2") (pinfunction "2_2") (pintype "passive"))
      (node (ref "R15") (pin "1") (pinfunction "1_1") (pintype "passive"))
      (node (ref "T1") (pin "4") (pinfunction "GND_4") (pintype "passive"))
    )
    (net (code "37") (name "Net-(T1-PRIMARY_DOT)") (class "Default")
      (node (ref "R13") (pin "1") (pinfunction "1_1") (pintype "passive"))
      (node (ref "R16") (pin "1") (pinfunction "1_1") (pintype "passive"))
      (node (ref "T1") (pin "6") (pinfunction "PRIMARY_DOT_6") (pintype "passive"))
    )
    (net (code "38") (name "Net-(T1-SECONDARY_DOT)") (class "Default")
      (node (ref "R17") (pin "1") (pinfunction "1_1") (pintype "passive"))
      (node (ref "T1") (pin "5") (pinfunction "SECONDARY_DOT_5") (pintype "passive"))
    )
    (net (code "39") (name "Net-(U1-ACG1)") (class "Default")
      (node (ref "C6") (pin "1") (pinfunction "1_1") (pintype "passive"))
      (node (ref "U1") (pin "4") (pinfunction "ACG1_4") (pintype "passive"))
      (node (ref "U1") (pin "5") (pinfunction "ACG2_5") (pintype "passive"))
      (node (ref "U1") (pin "6") (pinfunction "ACG3_6") (pintype "passive"))
      (node (ref "U1") (pin "7") (pinfunction "ACG4_7") (pintype "passive"))
      (node (ref "U1") (pin "8") (pinfunction "ACG5_8") (pintype "passive"))
    )
    (net (code "40") (name "Net-(U1-RF1)") (class "Default")
      (node (ref "C4") (pin "2") (pinfunction "2_2") (pintype "passive"))
      (node (ref "U1") (pin "2") (pinfunction "RF1_2") (pintype "passive"))
    )
    (net (code "41") (name "Net-(U1-RF2)") (class "Default")
      (node (ref "C2") (pin "1") (pinfunction "1_1") (pintype "passive"))
      (node (ref "U1") (pin "11") (pinfunction "RF2_11") (pintype "passive"))
    )
    (net (code "42") (name "Net-(U1-V1)") (class "Default")
      (node (ref "R10") (pin "1") (pinfunction "1_1") (pintype "passive"))
      (node (ref "U1") (pin "12") (pinfunction "V1_12") (pintype "passive"))
    )
    (net (code "43") (name "Net-(U1-V2)") (class "Default")
      (node (ref "R9") (pin "1") (pinfunction "1_1") (pintype "passive"))
      (node (ref "U1") (pin "13") (pinfunction "V2_13") (pintype "passive"))
    )
    (net (code "44") (name "Net-(U1-V3)") (class "Default")
      (node (ref "R8") (pin "1") (pinfunction "1_1") (pintype "passive"))
      (node (ref "U1") (pin "14") (pinfunction "V3_14") (pintype "passive"))
    )
    (net (code "45") (name "Net-(U1-V4)") (class "Default")
      (node (ref "R7") (pin "1") (pinfunction "1_1") (pintype "passive"))
      (node (ref "U1") (pin "15") (pinfunction "V4_15") (pintype "passive"))
    )
    (net (code "46") (name "Net-(U1-V5)") (class "Default")
      (node (ref "R6") (pin "1") (pinfunction "1_1") (pintype "passive"))
      (node (ref "U1") (pin "16") (pinfunction "V5_16") (pintype "passive"))
    )
    (net (code "47") (name "Net-(U2-VIN+)") (class "Default")
      (node (ref "C1") (pin "1") (pinfunction "1_1") (pintype "passive"))
      (node (ref "U2") (pin "2") (pinfunction "VIN+_2") (pintype "passive"))
    )
    (net (code "48") (name "Net-(U2-VIN-)") (class "Default")
      (node (ref "C2") (pin "2") (pinfunction "2_2") (pintype "passive"))
      (node (ref "U2") (pin "3") (pinfunction "VIN-_3") (pintype "passive"))
    )
    (net (code "49") (name "Net-(U2-VOUT+)") (class "Default")
      (node (ref "C7") (pin "2") (pinfunction "2_2") (pintype "passive"))
      (node (ref "U$5") (pin "2") (pinfunction "2_2") (pintype "passive"))
      (node (ref "U2") (pin "17") (pinfunction "VOUT+_17") (pintype "passive"))
    )
    (net (code "50") (name "Net-(U2-VOUT-)") (class "Default")
      (node (ref "C8") (pin "2") (pinfunction "2_2") (pintype "passive"))
      (node (ref "U$6") (pin "1") (pinfunction "1_1") (pintype "passive"))
      (node (ref "U2") (pin "16") (pinfunction "VOUT-_16") (pintype "passive"))
    )
    (net (code "51") (name "Net-(U3-ACG1)") (class "Default")
      (node (ref "C5") (pin "1") (pinfunction "1_1") (pintype "passive"))
      (node (ref "U3") (pin "4") (pinfunction "ACG1_4") (pintype "passive"))
      (node (ref "U3") (pin "5") (pinfunction "ACG2_5") (pintype "passive"))
      (node (ref "U3") (pin "6") (pinfunction "ACG3_6") (pintype "passive"))
      (node (ref "U3") (pin "7") (pinfunction "ACG4_7") (pintype "passive"))
      (node (ref "U3") (pin "8") (pinfunction "ACG5_8") (pintype "passive"))
    )
    (net (code "52") (name "Net-(U3-RF1)") (class "Default")
      (node (ref "C3") (pin "2") (pinfunction "2_2") (pintype "passive"))
      (node (ref "U3") (pin "2") (pinfunction "RF1_2") (pintype "passive"))
    )
    (net (code "53") (name "Net-(U3-RF2)") (class "Default")
      (node (ref "C1") (pin "2") (pinfunction "2_2") (pintype "passive"))
      (node (ref "U3") (pin "11") (pinfunction "RF2_11") (pintype "passive"))
    )
    (net (code "54") (name "Net-(U3-V1)") (class "Default")
      (node (ref "R5") (pin "1") (pinfunction "1_1") (pintype "passive"))
      (node (ref "U3") (pin "12") (pinfunction "V1_12") (pintype "passive"))
    )
    (net (code "55") (name "Net-(U3-V2)") (class "Default")
      (node (ref "R4") (pin "1") (pinfunction "1_1") (pintype "passive"))
      (node (ref "U3") (pin "13") (pinfunction "V2_13") (pintype "passive"))
    )
    (net (code "56") (name "Net-(U3-V3)") (class "Default")
      (node (ref "R3") (pin "1") (pinfunction "1_1") (pintype "passive"))
      (node (ref "U3") (pin "14") (pinfunction "V3_14") (pintype "passive"))
    )
    (net (code "57") (name "Net-(U3-V4)") (class "Default")
      (node (ref "R2") (pin "1") (pinfunction "1_1") (pintype "passive"))
      (node (ref "U3") (pin "15") (pinfunction "V4_15") (pintype "passive"))
    )
    (net (code "58") (name "Net-(U3-V5)") (class "Default")
      (node (ref "R1") (pin "1") (pinfunction "1_1") (pintype "passive"))
      (node (ref "U3") (pin "16") (pinfunction "V5_16") (pintype "passive"))
    )
    (net (code "59") (name "Net-(U4A-BOOT0)") (class "Default")
      (node (ref "R28") (pin "2") (pinfunction "2_2") (pintype "passive"))
      (node (ref "R29") (pin "2") (pinfunction "2_2") (pintype "passive"))
      (node (ref "U4") (pin "31") (pinfunction "BOOT0_31") (pintype "input"))
    )
    (net (code "60") (name "Net-(U4A-PC14-OSC32_IN)") (class "Default")
      (node (ref "R25") (pin "1") (pinfunction "1_1") (pintype "passive"))
      (node (ref "U4") (pin "2") (pinfunction "PC14-OSC32_IN_2") (pintype "bidirectional"))
    )
    (net (code "61") (name "Net-(U4A-PC15-OSC32_OUT)") (class "Default")
      (node (ref "R26") (pin "1") (pinfunction "1_1") (pintype "passive"))
      (node (ref "U4") (pin "3") (pinfunction "PC15-OSC32_OUT_3") (pintype "bidirectional"))
    )
    (net (code "62") (name "Net-(U5-J3)") (class "Default")
      (node (ref "U5") (pin "1") (pinfunction "J3_1") (pintype "passive"))
      (node (ref "X3") (pin "P") (pinfunction "ANT_P") (pintype "bidirectional"))
    )
    (net (code "63") (name "Net-(U7-IN_A)") (class "Default")
      (node (ref "U7") (pin "23") (pinfunction "IN_A_23") (pintype "passive"))
      (node (ref "U7") (pin "27") (pinfunction "OUT_A_27") (pintype "output"))
    )
    (net (code "64") (name "Net-(U7-IN_B)") (class "Default")
      (node (ref "U7") (pin "13") (pinfunction "IN_B_13") (pintype "passive"))
      (node (ref "U7") (pin "9") (pinfunction "OUT_B_9") (pintype "output"))
    )
    (net (code "65") (name "Net-(U7-RFIN)") (class "Default")
      (node (ref "C26") (pin "2") (pinfunction "2_2") (pintype "passive"))
      (node (ref "U7") (pin "4") (pinfunction "RFIN_4") (pintype "passive"))
    )
    (net (code "66") (name "Net-(U7-RFOUT)") (class "Default")
      (node (ref "C23") (pin "1") (pinfunction "1_1") (pintype "passive"))
      (node (ref "U7") (pin "18") (pinfunction "RFOUT_18") (pintype "output"))
    )
    (net (code "67") (name "Net-(U7-VBIAS)") (class "Default")
      (node (ref "R30") (pin "1") (pinfunction "1_1") (pintype "passive"))
      (node (ref "U7") (pin "2") (pinfunction "VBIAS_2") (pintype "passive"))
    )
    (net (code "68") (name "Net-(U8-CAP+)") (class "Default")
      (node (ref "C24") (pin "1") (pinfunction "1_1") (pintype "passive"))
      (node (ref "U8") (pin "2") (pinfunction "CAP+_2") (pintype "passive"))
    )
    (net (code "69") (name "Net-(U8-CAP-)") (class "Default")
      (node (ref "C24") (pin "2") (pinfunction "2_2") (pintype "passive"))
      (node (ref "U8") (pin "4") (pinfunction "CAP-_4") (pintype "passive"))
    )
    (net (code "70") (name "Net-(U8-OSC)") (class "Default")
      (node (ref "N$29") (pin "2") (pinfunction "2_2") (pintype "passive"))
      (node (ref "U8") (pin "7") (pinfunction "OSC_7") (pintype "passive"))
    )
    (net (code "71") (name "Net-(X1-ANT)") (class "Default")
      (node (ref "C3") (pin "1") (pinfunction "1_1") (pintype "passive"))
      (node (ref "X1") (pin "P") (pinfunction "ANT_P") (pintype "bidirectional"))
    )
    (net (code "72") (name "Net-(X2-ANT)") (class "Default")
      (node (ref "C4") (pin "1") (pinfunction "1_1") (pintype "passive"))
      (node (ref "X2") (pin "P") (pinfunction "ANT_P") (pintype "bidirectional"))
    )
    (net (code "73") (name "unconnected-(U2-DNC-Pad18)") (class "Default")
      (node (ref "U2") (pin "18") (pinfunction "DNC_18") (pintype "passive"))
    )
    (net (code "74") (name "unconnected-(U2-DNC_2-Pad14)") (class "Default")
      (node (ref "U2") (pin "14") (pinfunction "DNC_2_14") (pintype "passive"))
    )
    (net (code "75") (name "unconnected-(U2-DNC_3-Pad15)") (class "Default")
      (node (ref "U2") (pin "15") (pinfunction "DNC_3_15") (pintype "passive"))
    )
    (net (code "76") (name "unconnected-(U8-NC-Pad1)") (class "Default")
      (node (ref "U8") (pin "1") (pinfunction "NC_1") (pintype "passive"))
    )
  )
)
